# Flash.net
KiCad netlist of a schematic drawn in Altium Designer
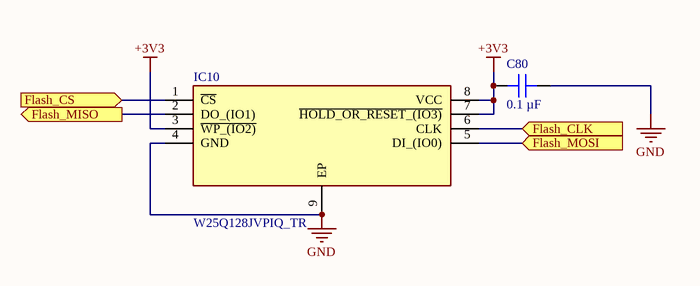
[diagram p0: Flash.SchDoc]

(export (version "E")
  (design (tool "Eeschema 10.0.6"))
  (components
    (comp (ref "C80")
      (value "0.1 µF")
      (footprint "CAP 0402_1005")
      (description "CAP CER 0402 0.1UF 16V X7R 10%")
      (fields
        (field (name "PART NUMBER") "C0402C104K4RECAUTO")
        (field (name "CAPACITANCE") "0.1 µF")
        (field (name "MANUFACTURER") "KEMET")
      )
      (libsource (lib "Celestial Altium Library - altium_library") (part "Capacitor"))
    )
    (comp (ref "IC10")
      (value "W25Q128JVPIQ_TR")
      (footprint "PcbLib1:SON127P600X500X80-9N-D")
      (description "Integrated Circuit")
      (fields
        (field (name "MANUFACTURER_PART_NUMBER") "W25Q128JVPIQ TR")
        (field (name "MOUSER PART NUMBER") "454-W25Q128JVPIQTR")
      )
      (libsource (lib "*") (part "W25Q128JVPIQ_TR"))
    )
  )
  (nets
    (net (code "1") (name "+3V3") (class "Default")
      (node (ref "C80") (pin "1") (pinfunction "1_1") (pintype "passive"))
      (node (ref "IC10") (pin "3") (pinfunction "~{WP_(IO2)}_3") (pintype "passive"))
      (node (ref "IC10") (pin "7") (pinfunction "~{HOLD_OR_RESET_(IO3)}_7") (pintype "passive"))
      (node (ref "IC10") (pin "8") (pinfunction "VCC_8") (pintype "passive"))
    )
    (net (code "2") (name "/Flash_CLK") (class "Default")
      (node (ref "IC10") (pin "6") (pinfunction "CLK_6") (pintype "passive"))
    )
    (net (code "3") (name "/Flash_CS") (class "Default")
      (node (ref "IC10") (pin "1") (pinfunction "~{CS}_1") (pintype "passive"))
    )
    (net (code "4") (name "/Flash_MISO") (class "Default")
      (node (ref "IC10") (pin "2") (pinfunction "DO_(IO1)_2") (pintype "passive"))
    )
    (net (code "5") (name "/Flash_MOSI") (class "Default")
      (node (ref "IC10") (pin "5") (pinfunction "DI_(IO0)_5") (pintype "passive"))
    )
    (net (code "6") (name "GND") (class "Default")
      (node (ref "C80") (pin "2") (pinfunction "2_2") (pintype "passive"))
      (node (ref "IC10") (pin "4") (pinfunction "GND_4") (pintype "passive"))
      (node (ref "IC10") (pin "9") (pinfunction "EP_9") (pintype "passive"))
    )
  )
)
